# SHY-BOTTOM.net
KiCad netlist of a schematic drawn in EAGLE
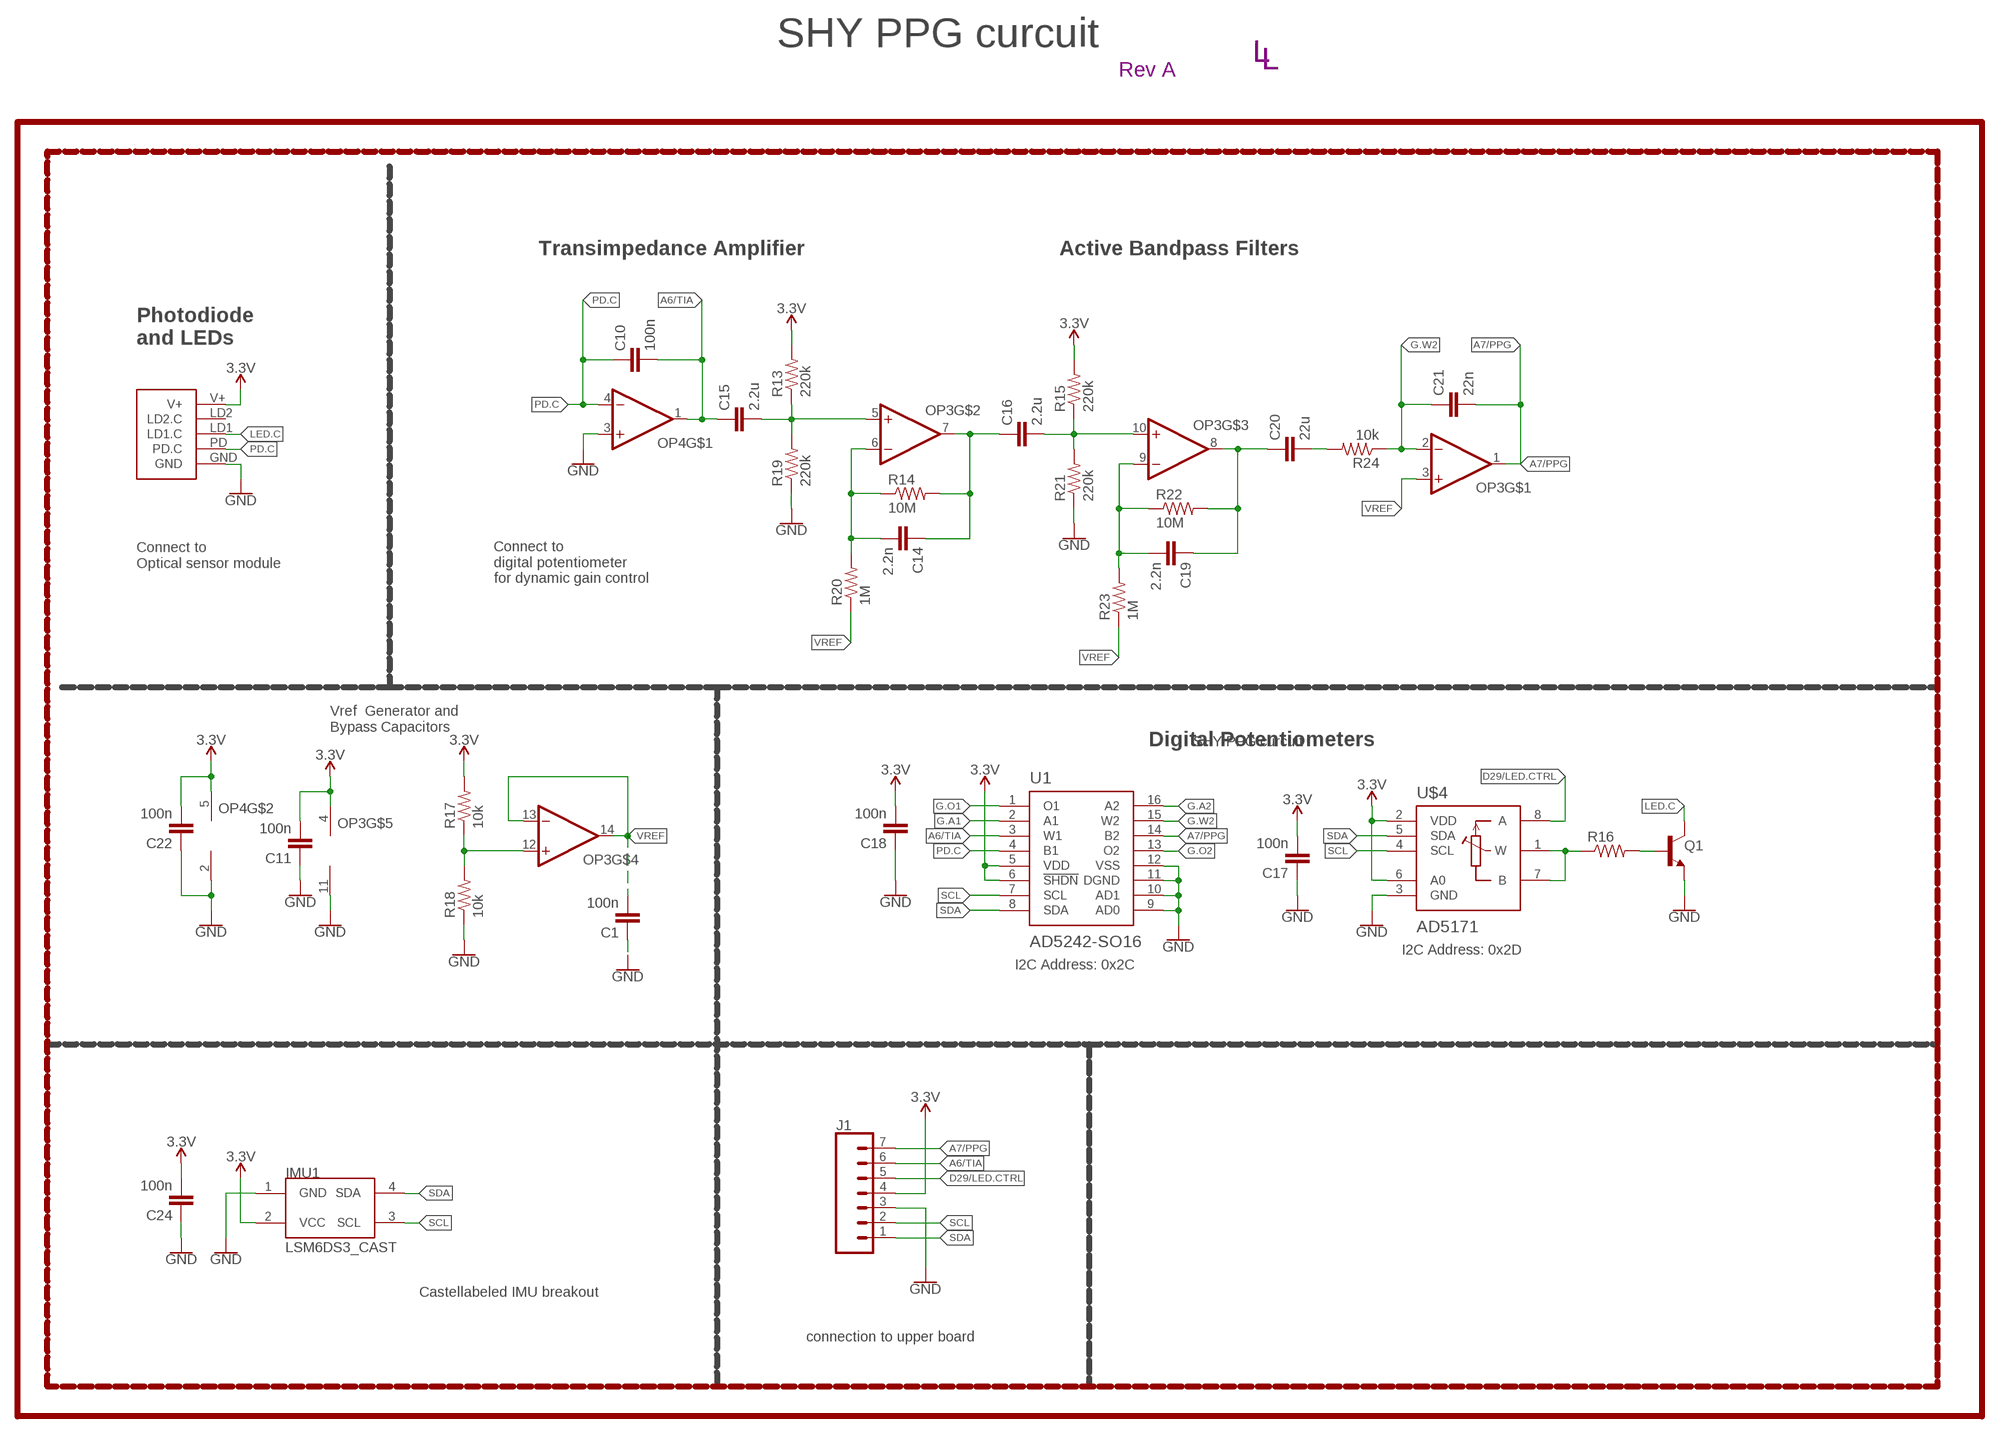
[diagram p0: schematic, sheet 1]

(export (version "E")
  (design (tool "Eeschema 10.0.6"))
  (components
    (comp (ref "C1")
      (value "100n")
      (footprint "eagle-import:C0603")
      (libsource (lib "eagle-import") (part "CAPACITOR0603"))
    )
    (comp (ref "C10")
      (value "100n")
      (footprint "eagle-import:C0603")
      (libsource (lib "eagle-import") (part "CAPACITOR0603"))
    )
    (comp (ref "C11")
      (value "100n")
      (footprint "eagle-import:C0603")
      (libsource (lib "eagle-import") (part "CAPACITOR0603"))
    )
    (comp (ref "C14")
      (value "2.2n")
      (footprint "eagle-import:C0603")
      (libsource (lib "eagle-import") (part "CAPACITOR0603"))
    )
    (comp (ref "C15")
      (value "2.2u")
      (footprint "eagle-import:C0603")
      (libsource (lib "eagle-import") (part "CAPACITOR0603"))
    )
    (comp (ref "C16")
      (value "2.2u")
      (footprint "eagle-import:C0603")
      (libsource (lib "eagle-import") (part "CAPACITOR0603"))
    )
    (comp (ref "C17")
      (value "100n")
      (footprint "eagle-import:C0603")
      (libsource (lib "eagle-import") (part "CAPACITOR0603"))
    )
    (comp (ref "C18")
      (value "100n")
      (footprint "eagle-import:C0603")
      (libsource (lib "eagle-import") (part "CAPACITOR0603"))
    )
    (comp (ref "C19")
      (value "2.2n")
      (footprint "eagle-import:C0603")
      (libsource (lib "eagle-import") (part "CAPACITOR0603"))
    )
    (comp (ref "C20")
      (value "22u")
      (footprint "eagle-import:C0603")
      (libsource (lib "eagle-import") (part "CAPACITOR0603"))
    )
    (comp (ref "C21")
      (value "22n")
      (footprint "eagle-import:C0603")
      (libsource (lib "eagle-import") (part "CAPACITOR0603"))
    )
    (comp (ref "C22")
      (value "100n")
      (footprint "eagle-import:C0603")
      (libsource (lib "eagle-import") (part "CAPACITOR0603"))
    )
    (comp (ref "C24")
      (value "100n")
      (footprint "eagle-import:C0603")
      (libsource (lib "eagle-import") (part "CAPACITOR0603"))
    )
    (comp (ref "IMU1")
      (value "LSM6DS3_CAST")
      (footprint "eagle-import:LSM6DS3_CAST")
      (libsource (lib "eagle-import") (part "LSM6DS3_CAST"))
    )
    (comp (ref "J1")
      (value "CONN_07-1.27MM")
      (footprint "eagle-import:1X07_1.27MM")
      (libsource (lib "eagle-import") (part "CONN_07-1.27MM"))
    )
    (comp (ref "LOGO1")
      (value "REVISION.A")
      (footprint "eagle-import:REV.A")
      (libsource (lib "eagle-import") (part "REVISION.A"))
    )
    (comp (ref "LOGO2")
      (value "LINNES.LAB.LOGO")
      (footprint "eagle-import:LINNES.LAB.LOGO")
      (libsource (lib "eagle-import") (part "LINNES.LAB.LOGO"))
    )
    (comp (ref "OP3")
      (value "OP-QUAD-SO14")
      (footprint "eagle-import:SO14")
      (libsource (lib "eagle-import") (part "OP-QUAD-SO14"))
    )
    (comp (ref "OP4")
      (value "OP-SINGLEOT")
      (footprint "eagle-import:SOT23-5")
      (libsource (lib "eagle-import") (part "OP-SINGLEOT"))
    )
    (comp (ref "Q1")
      (value "NPN-GENERIC")
      (footprint "eagle-import:SOT23-3")
      (libsource (lib "eagle-import") (part "NPN-GENERIC"))
    )
    (comp (ref "R13")
      (value "220k")
      (footprint "eagle-import:R0603")
      (libsource (lib "eagle-import") (part "RESISTOR0603"))
    )
    (comp (ref "R14")
      (value "10M")
      (footprint "eagle-import:R0603")
      (libsource (lib "eagle-import") (part "RESISTOR0603"))
    )
    (comp (ref "R15")
      (value "220k")
      (footprint "eagle-import:R0603")
      (libsource (lib "eagle-import") (part "RESISTOR0603"))
    )
    (comp (ref "R16")
      (value "RESISTOR0603")
      (footprint "eagle-import:R0603")
      (libsource (lib "eagle-import") (part "RESISTOR0603"))
    )
    (comp (ref "R17")
      (value "10k")
      (footprint "eagle-import:R0402")
      (libsource (lib "eagle-import") (part "RESISTOR0402"))
    )
    (comp (ref "R18")
      (value "10k")
      (footprint "eagle-import:R0402")
      (libsource (lib "eagle-import") (part "RESISTOR0402"))
    )
    (comp (ref "R19")
      (value "220k")
      (footprint "eagle-import:R0603")
      (libsource (lib "eagle-import") (part "RESISTOR0603"))
    )
    (comp (ref "R20")
      (value "1M")
      (footprint "eagle-import:R0603")
      (libsource (lib "eagle-import") (part "RESISTOR0603"))
    )
    (comp (ref "R21")
      (value "220k")
      (footprint "eagle-import:R0603")
      (libsource (lib "eagle-import") (part "RESISTOR0603"))
    )
    (comp (ref "R22")
      (value "10M")
      (footprint "eagle-import:R0603")
      (libsource (lib "eagle-import") (part "RESISTOR0603"))
    )
    (comp (ref "R23")
      (value "1M")
      (footprint "eagle-import:R0603")
      (libsource (lib "eagle-import") (part "RESISTOR0603"))
    )
    (comp (ref "R24")
      (value "10k")
      (footprint "eagle-import:R0603")
      (libsource (lib "eagle-import") (part "RESISTOR0603"))
    )
    (comp (ref "U$3")
      (value "PPG.MODULE.2")
      (footprint "eagle-import:PPG.MODULE.2")
      (libsource (lib "eagle-import") (part "PPG.MODULE.2"))
    )
    (comp (ref "U$4")
      (value "AD5171")
      (footprint "eagle-import:SOT-23-8")
      (libsource (lib "eagle-import") (part "AD5171"))
    )
    (comp (ref "U1")
      (value "AD5242-SO16")
      (footprint "eagle-import:SO16")
      (libsource (lib "eagle-import") (part "AD5242-SO16"))
    )
  )
  (nets
    (net (code "1") (name "3.3V") (class "Default")
      (node (ref "C11") (pin "2") (pinfunction "2_2") (pintype "passive"))
      (node (ref "C17") (pin "2") (pinfunction "2_2") (pintype "passive"))
      (node (ref "C18") (pin "2") (pinfunction "2_2") (pintype "passive"))
      (node (ref "C22") (pin "2") (pinfunction "2_2") (pintype "passive"))
      (node (ref "C24") (pin "2") (pinfunction "2_2") (pintype "passive"))
      (node (ref "IMU1") (pin "2") (pinfunction "VCC_2") (pintype "bidirectional"))
      (node (ref "J1") (pin "4") (pinfunction "4_4") (pintype "passive"))
      (node (ref "OP3") (pin "4") (pinfunction "V+_4") (pintype "power_in"))
      (node (ref "OP4") (pin "5") (pinfunction "V+_5") (pintype "power_in"))
      (node (ref "R13") (pin "2") (pinfunction "2_2") (pintype "passive"))
      (node (ref "R15") (pin "2") (pinfunction "2_2") (pintype "passive"))
      (node (ref "R17") (pin "2") (pinfunction "2_2") (pintype "passive"))
      (node (ref "U$3") (pin "V+") (pinfunction "V+_V+") (pintype "bidirectional"))
      (node (ref "U$4") (pin "2") (pinfunction "VDD_2") (pintype "bidirectional"))
      (node (ref "U$4") (pin "6") (pinfunction "A0_6") (pintype "bidirectional"))
      (node (ref "U1") (pin "5") (pinfunction "VDD_5") (pintype "bidirectional"))
      (node (ref "U1") (pin "6") (pinfunction "~{SHDN}_6") (pintype "bidirectional"))
    )
    (net (code "2") (name "A6{slash}TIA") (class "Default")
      (node (ref "C10") (pin "2") (pinfunction "2_2") (pintype "passive"))
      (node (ref "C15") (pin "1") (pinfunction "1_1") (pintype "passive"))
      (node (ref "J1") (pin "6") (pinfunction "6_6") (pintype "passive"))
      (node (ref "OP4") (pin "1") (pinfunction "OUT_1") (pintype "output"))
      (node (ref "U1") (pin "3") (pinfunction "W1_3") (pintype "bidirectional"))
    )
    (net (code "3") (name "A7{slash}PPG") (class "Default")
      (node (ref "C21") (pin "2") (pinfunction "2_2") (pintype "passive"))
      (node (ref "J1") (pin "7") (pinfunction "7_7") (pintype "passive"))
      (node (ref "OP3") (pin "1") (pinfunction "OUT_1") (pintype "output"))
      (node (ref "U1") (pin "14") (pinfunction "B2_14") (pintype "bidirectional"))
    )
    (net (code "4") (name "D29{slash}LED.CTRL") (class "Default")
      (node (ref "J1") (pin "5") (pinfunction "5_5") (pintype "passive"))
      (node (ref "U$4") (pin "8") (pinfunction "A_8") (pintype "bidirectional"))
    )
    (net (code "5") (name "G.A1") (class "Default")
      (node (ref "U1") (pin "2") (pinfunction "A1_2") (pintype "bidirectional"))
    )
    (net (code "6") (name "G.A2") (class "Default")
      (node (ref "U1") (pin "16") (pinfunction "A2_16") (pintype "bidirectional"))
    )
    (net (code "7") (name "G.O1") (class "Default")
      (node (ref "U1") (pin "1") (pinfunction "O1_1") (pintype "bidirectional"))
    )
    (net (code "8") (name "G.O2") (class "Default")
      (node (ref "U1") (pin "13") (pinfunction "O2_13") (pintype "bidirectional"))
    )
    (net (code "9") (name "G.W2") (class "Default")
      (node (ref "C21") (pin "1") (pinfunction "1_1") (pintype "passive"))
      (node (ref "OP3") (pin "2") (pinfunction "-IN_2") (pintype "input"))
      (node (ref "R24") (pin "1") (pinfunction "1_1") (pintype "passive"))
      (node (ref "U1") (pin "15") (pinfunction "W2_15") (pintype "bidirectional"))
    )
    (net (code "10") (name "GND") (class "Default")
      (node (ref "C1") (pin "1") (pinfunction "1_1") (pintype "passive"))
      (node (ref "C11") (pin "1") (pinfunction "1_1") (pintype "passive"))
      (node (ref "C17") (pin "1") (pinfunction "1_1") (pintype "passive"))
      (node (ref "C18") (pin "1") (pinfunction "1_1") (pintype "passive"))
      (node (ref "C22") (pin "1") (pinfunction "1_1") (pintype "passive"))
      (node (ref "C24") (pin "1") (pinfunction "1_1") (pintype "passive"))
      (node (ref "IMU1") (pin "1") (pinfunction "GND_1") (pintype "bidirectional"))
      (node (ref "J1") (pin "3") (pinfunction "3_3") (pintype "passive"))
      (node (ref "OP3") (pin "11") (pinfunction "V-_11") (pintype "power_in"))
      (node (ref "OP4") (pin "2") (pinfunction "V-_2") (pintype "power_in"))
      (node (ref "OP4") (pin "3") (pinfunction "+IN_3") (pintype "input"))
      (node (ref "Q1") (pin "2") (pinfunction "E_2") (pintype "passive"))
      (node (ref "R18") (pin "1") (pinfunction "1_1") (pintype "passive"))
      (node (ref "R19") (pin "1") (pinfunction "1_1") (pintype "passive"))
      (node (ref "R21") (pin "1") (pinfunction "1_1") (pintype "passive"))
      (node (ref "U$3") (pin "GND") (pinfunction "GND_GND") (pintype "bidirectional"))
      (node (ref "U$4") (pin "3") (pinfunction "GND_3") (pintype "bidirectional"))
      (node (ref "U1") (pin "10") (pinfunction "AD1_10") (pintype "bidirectional"))
      (node (ref "U1") (pin "11") (pinfunction "DGND_11") (pintype "bidirectional"))
      (node (ref "U1") (pin "12") (pinfunction "VSS_12") (pintype "bidirectional"))
      (node (ref "U1") (pin "9") (pinfunction "AD0_9") (pintype "bidirectional"))
    )
    (net (code "11") (name "LED.C") (class "Default")
      (node (ref "Q1") (pin "3") (pinfunction "C_3") (pintype "passive"))
      (node (ref "U$3") (pin "LD1") (pinfunction "LD1.C_LD1") (pintype "bidirectional"))
    )
    (net (code "12") (name "Net-(C20-Pad2)") (class "Default")
      (node (ref "C20") (pin "2") (pinfunction "2_2") (pintype "passive"))
      (node (ref "R24") (pin "2") (pinfunction "2_2") (pintype "passive"))
    )
    (net (code "13") (name "Net-(OP3B-+IN)") (class "Default")
      (node (ref "C15") (pin "2") (pinfunction "2_2") (pintype "passive"))
      (node (ref "OP3") (pin "5") (pinfunction "+IN_5") (pintype "input"))
      (node (ref "R13") (pin "1") (pinfunction "1_1") (pintype "passive"))
      (node (ref "R19") (pin "2") (pinfunction "2_2") (pintype "passive"))
    )
    (net (code "14") (name "Net-(OP3B--IN)") (class "Default")
      (node (ref "C14") (pin "2") (pinfunction "2_2") (pintype "passive"))
      (node (ref "OP3") (pin "6") (pinfunction "-IN_6") (pintype "input"))
      (node (ref "R14") (pin "1") (pinfunction "1_1") (pintype "passive"))
      (node (ref "R20") (pin "2") (pinfunction "2_2") (pintype "passive"))
    )
    (net (code "15") (name "Net-(OP3B-OUT)") (class "Default")
      (node (ref "C14") (pin "1") (pinfunction "1_1") (pintype "passive"))
      (node (ref "C16") (pin "1") (pinfunction "1_1") (pintype "passive"))
      (node (ref "OP3") (pin "7") (pinfunction "OUT_7") (pintype "output"))
      (node (ref "R14") (pin "2") (pinfunction "2_2") (pintype "passive"))
    )
    (net (code "16") (name "Net-(OP3C-+IN)") (class "Default")
      (node (ref "C16") (pin "2") (pinfunction "2_2") (pintype "passive"))
      (node (ref "OP3") (pin "10") (pinfunction "+IN_10") (pintype "input"))
      (node (ref "R15") (pin "1") (pinfunction "1_1") (pintype "passive"))
      (node (ref "R21") (pin "2") (pinfunction "2_2") (pintype "passive"))
    )
    (net (code "17") (name "Net-(OP3C--IN)") (class "Default")
      (node (ref "C19") (pin "2") (pinfunction "2_2") (pintype "passive"))
      (node (ref "OP3") (pin "9") (pinfunction "-IN_9") (pintype "input"))
      (node (ref "R22") (pin "1") (pinfunction "1_1") (pintype "passive"))
      (node (ref "R23") (pin "2") (pinfunction "2_2") (pintype "passive"))
    )
    (net (code "18") (name "Net-(OP3C-OUT)") (class "Default")
      (node (ref "C19") (pin "1") (pinfunction "1_1") (pintype "passive"))
      (node (ref "C20") (pin "1") (pinfunction "1_1") (pintype "passive"))
      (node (ref "OP3") (pin "8") (pinfunction "OUT_8") (pintype "output"))
      (node (ref "R22") (pin "2") (pinfunction "2_2") (pintype "passive"))
    )
    (net (code "19") (name "Net-(OP3D-+IN)") (class "Default")
      (node (ref "OP3") (pin "12") (pinfunction "+IN_12") (pintype "input"))
      (node (ref "R17") (pin "1") (pinfunction "1_1") (pintype "passive"))
      (node (ref "R18") (pin "2") (pinfunction "2_2") (pintype "passive"))
    )
    (net (code "20") (name "Net-(Q1-B)") (class "Default")
      (node (ref "Q1") (pin "1") (pinfunction "B_1") (pintype "passive"))
      (node (ref "R16") (pin "2") (pinfunction "2_2") (pintype "passive"))
    )
    (net (code "21") (name "Net-(U$4-B)") (class "Default")
      (node (ref "R16") (pin "1") (pinfunction "1_1") (pintype "passive"))
      (node (ref "U$4") (pin "1") (pinfunction "W_1") (pintype "bidirectional"))
      (node (ref "U$4") (pin "7") (pinfunction "B_7") (pintype "bidirectional"))
    )
    (net (code "22") (name "PD.C") (class "Default")
      (node (ref "C10") (pin "1") (pinfunction "1_1") (pintype "passive"))
      (node (ref "OP4") (pin "4") (pinfunction "-IN_4") (pintype "input"))
      (node (ref "U$3") (pin "PD") (pinfunction "PD.C_PD") (pintype "bidirectional"))
      (node (ref "U1") (pin "4") (pinfunction "B1_4") (pintype "bidirectional"))
    )
    (net (code "23") (name "SCL") (class "Default")
      (node (ref "IMU1") (pin "3") (pinfunction "SCL_3") (pintype "bidirectional"))
      (node (ref "J1") (pin "2") (pinfunction "2_2") (pintype "passive"))
      (node (ref "U$4") (pin "4") (pinfunction "SCL_4") (pintype "bidirectional"))
      (node (ref "U1") (pin "7") (pinfunction "SCL_7") (pintype "bidirectional"))
    )
    (net (code "24") (name "SDA") (class "Default")
      (node (ref "IMU1") (pin "4") (pinfunction "SDA_4") (pintype "bidirectional"))
      (node (ref "J1") (pin "1") (pinfunction "1_1") (pintype "passive"))
      (node (ref "U$4") (pin "5") (pinfunction "SDA_5") (pintype "bidirectional"))
      (node (ref "U1") (pin "8") (pinfunction "SDA_8") (pintype "bidirectional"))
    )
    (net (code "25") (name "VREF") (class "Default")
      (node (ref "C1") (pin "2") (pinfunction "2_2") (pintype "passive"))
      (node (ref "OP3") (pin "13") (pinfunction "-IN_13") (pintype "input"))
      (node (ref "OP3") (pin "14") (pinfunction "OUT_14") (pintype "output"))
      (node (ref "OP3") (pin "3") (pinfunction "+IN_3") (pintype "input"))
      (node (ref "R20") (pin "1") (pinfunction "1_1") (pintype "passive"))
      (node (ref "R23") (pin "1") (pinfunction "1_1") (pintype "passive"))
    )
    (net (code "26") (name "unconnected-(U$3-LD2.C-PadLD2)") (class "Default")
      (node (ref "U$3") (pin "LD2") (pinfunction "LD2.C_LD2") (pintype "bidirectional"))
    )
  )
)
